# Violet_Usb_Hub.net
KiCad netlist of a schematic drawn in EasyEDA Pro
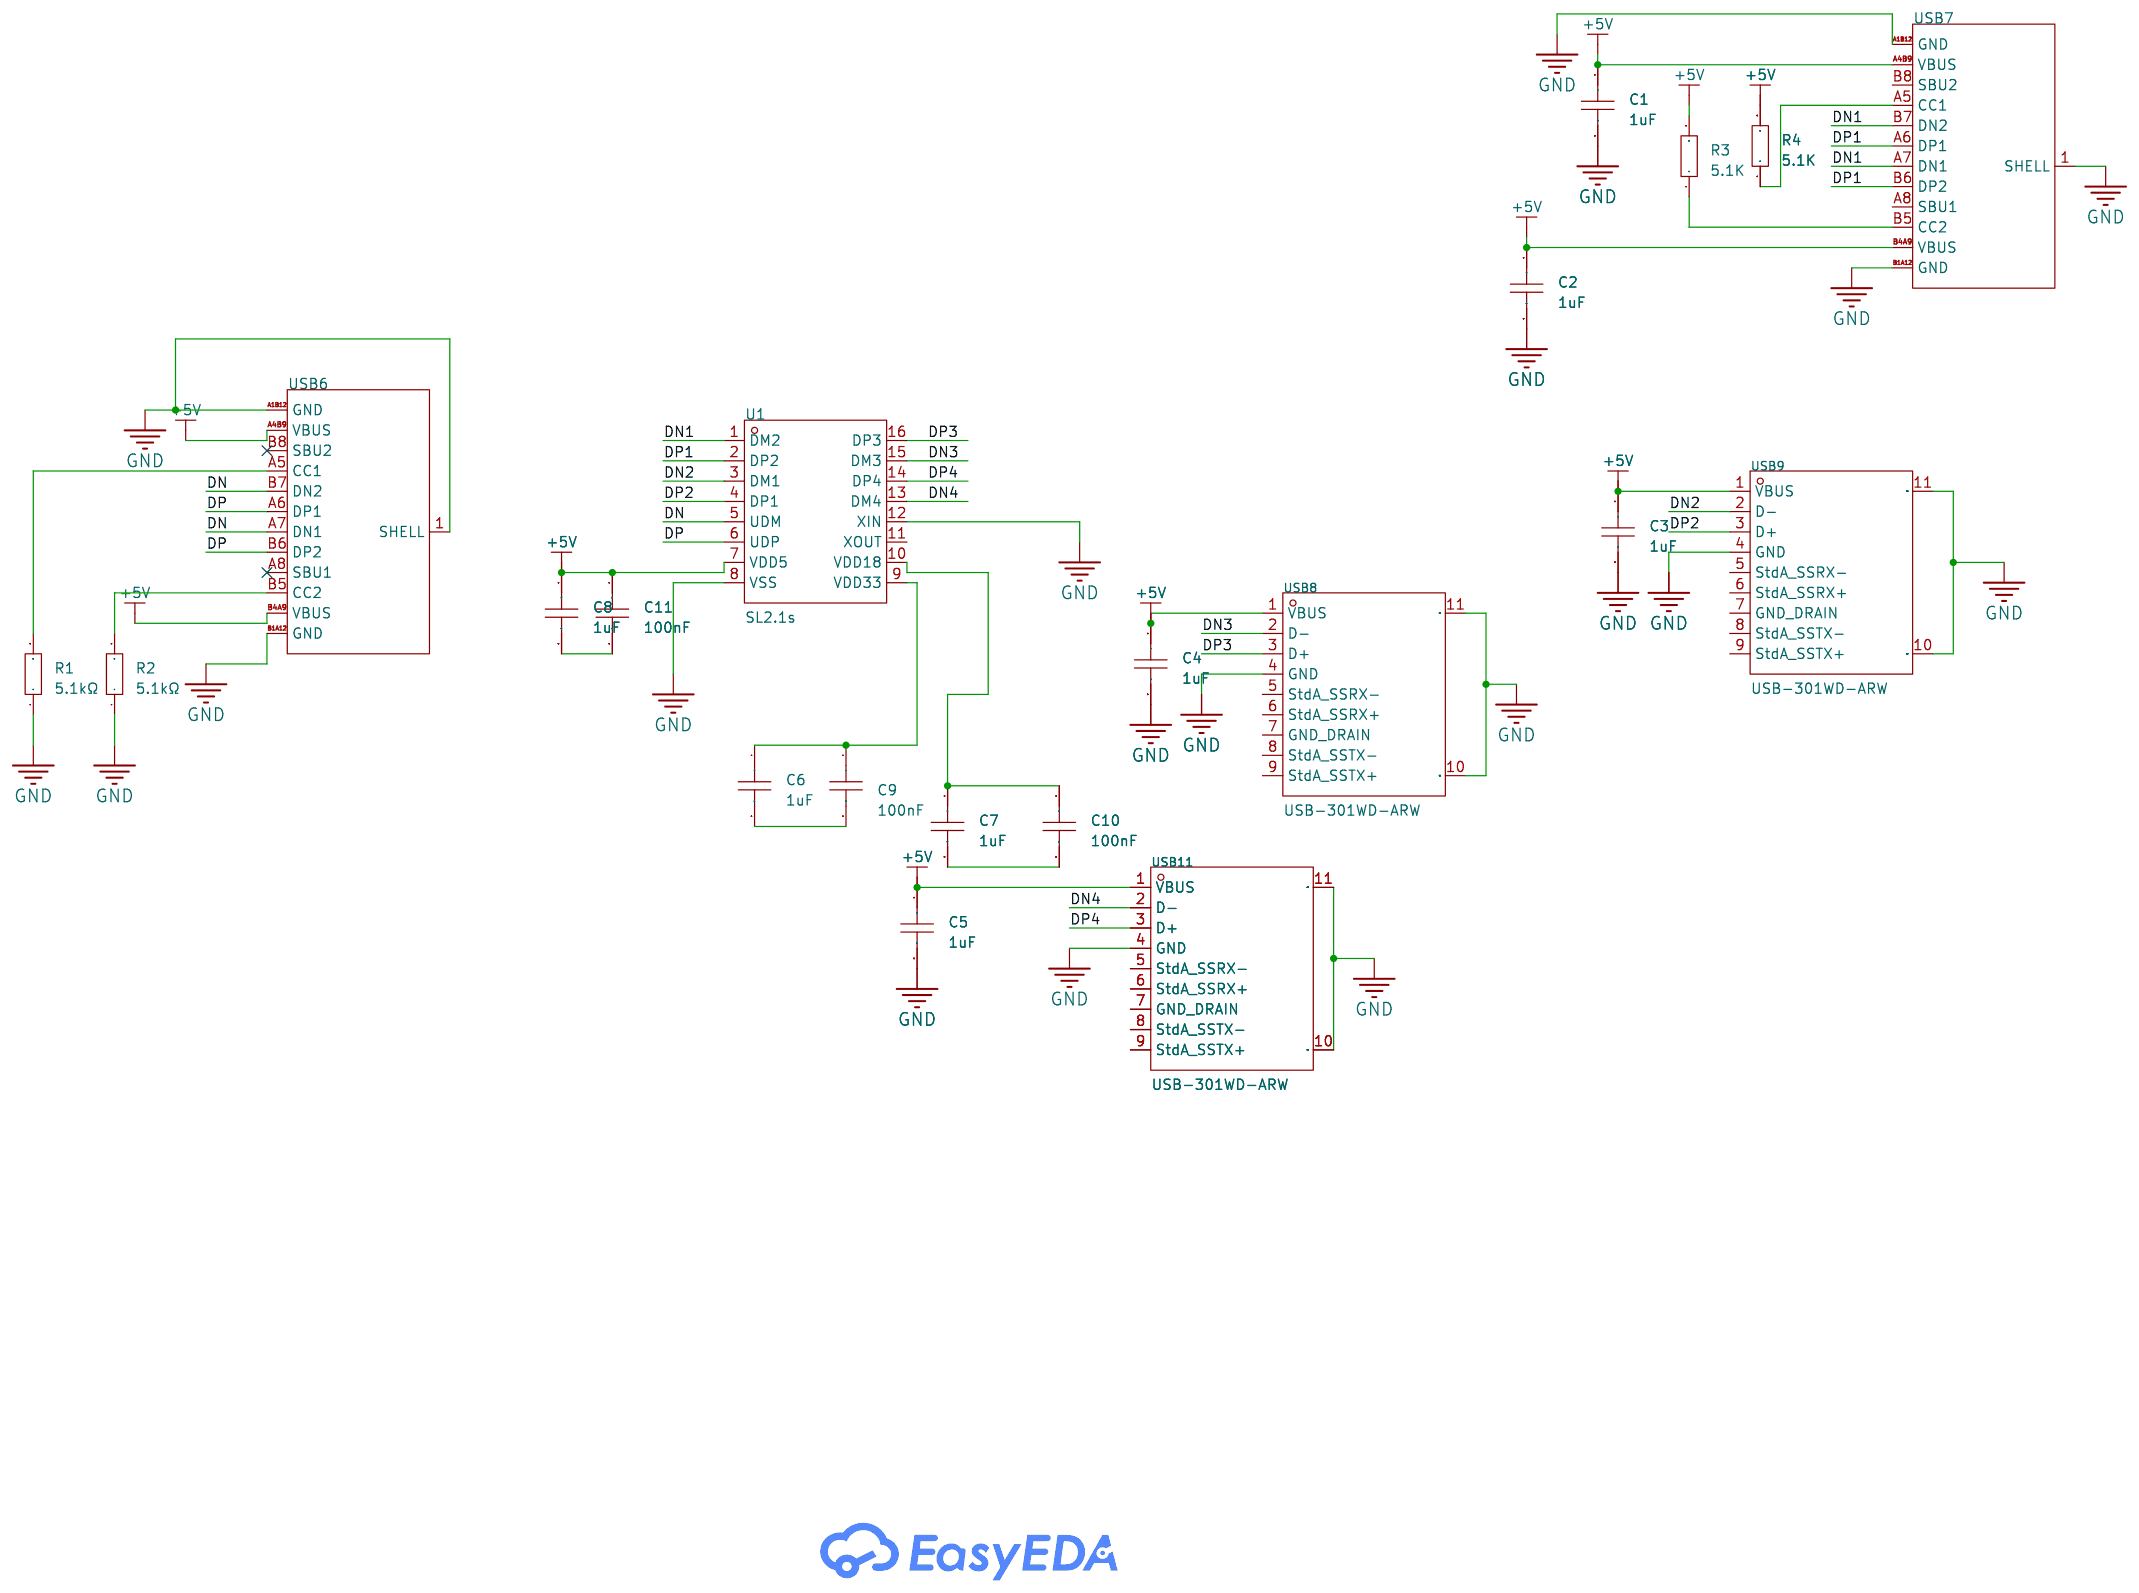
[diagram p0: schematic sheet]

(export (version "E")
  (design (tool "Eeschema 10.0.6"))
  (components
    (comp (ref "C1") (value "1uF") (footprint "easyedapro:C0603") (libsource (lib "easyedapro") (part "CAP")))
    (comp (ref "C2") (value "1uF") (footprint "easyedapro:C0603") (libsource (lib "easyedapro") (part "CAP")))
    (comp (ref "C3") (value "1uF") (footprint "easyedapro:C0603") (libsource (lib "easyedapro") (part "CAP")))
    (comp (ref "C4") (value "1uF") (footprint "easyedapro:C0603") (libsource (lib "easyedapro") (part "CAP")))
    (comp (ref "C5") (value "1uF") (footprint "easyedapro:C0603") (libsource (lib "easyedapro") (part "CAP")))
    (comp (ref "C6") (value "1uF") (footprint "easyedapro:C0603") (libsource (lib "easyedapro") (part "CAP")))
    (comp (ref "C7") (value "1uF") (footprint "easyedapro:C0603") (libsource (lib "easyedapro") (part "CAP")))
    (comp (ref "C8") (value "1uF") (footprint "easyedapro:C0603") (libsource (lib "easyedapro") (part "CAP")))
    (comp (ref "C9")
      (value "100nF")
      (footprint "easyedapro:C0603")
      (libsource (lib "easyedapro") (part "CAP"))
    )
    (comp (ref "C10")
      (value "100nF")
      (footprint "easyedapro:C0603")
      (libsource (lib "easyedapro") (part "CAP"))
    )
    (comp (ref "C11")
      (value "100nF")
      (footprint "easyedapro:C0603")
      (libsource (lib "easyedapro") (part "CAP"))
    )
    (comp (ref "R1")
      (value "5.1kΩ")
      (footprint "easyedapro:R0603")
      (libsource (lib "easyedapro") (part "Res"))
    )
    (comp (ref "R2")
      (value "5.1kΩ")
      (footprint "easyedapro:R0603")
      (libsource (lib "easyedapro") (part "Res"))
    )
    (comp (ref "R3")
      (value "5.1K")
      (footprint "easyedapro:R0603")
      (libsource (lib "easyedapro") (part "Res"))
    )
    (comp (ref "R4")
      (value "5.1K")
      (footprint "easyedapro:R0603")
      (libsource (lib "easyedapro") (part "Res"))
    )
    (comp (ref "U1")
      (value "SL2.1s")
      (footprint "easyedapro:SSOP-16_L4.6-W2.6-P0.53-LS4.0-BL")
      (fields (field (name "Manufacturer") "CoreChips(和芯润德)"))
      (libsource (lib "easyedapro") (part "SL2.1S"))
    )
    (comp (ref "USB6")
      (value "JBL-104312272-E")
      (footprint "easyedapro:USB-C-SMD_JBL-104312272-E")
      (fields (field (name "Manufacturer") "JBL(金比莱)"))
      (libsource (lib "easyedapro") (part "JBL-104312272-E"))
    )
    (comp (ref "USB7")
      (value "JBL-104312272-E")
      (footprint "easyedapro:USB-C-SMD_JBL-104312272-E")
      (fields (field (name "Manufacturer") "JBL(金比莱)"))
      (libsource (lib "easyedapro") (part "JBL-104312272-E"))
    )
    (comp (ref "USB8")
      (value "USB-301WD-ARW")
      (footprint "easyedapro:USB-TH_XUNPU_USB-301WD-ARW")
      (fields (field (name "Manufacturer") "XUNPU(讯普)"))
      (libsource (lib "easyedapro") (part "USB-301WD-ARW"))
    )
    (comp (ref "USB9")
      (value "USB-301WD-ARW")
      (footprint "easyedapro:USB-TH_XUNPU_USB-301WD-ARW")
      (fields (field (name "Manufacturer") "XUNPU(讯普)"))
      (libsource (lib "easyedapro") (part "USB-301WD-ARW"))
    )
    (comp (ref "USB11")
      (value "USB-301WD-ARW")
      (footprint "easyedapro:USB-TH_XUNPU_USB-301WD-ARW")
      (fields (field (name "Manufacturer") "XUNPU(讯普)"))
      (libsource (lib "easyedapro") (part "USB-301WD-ARW"))
    )
  )
  (nets
    (net (code "1") (name "+5V") (class "Default")
      (node (ref "C1") (pin "1") (pinfunction "1_1") (pintype "input"))
      (node (ref "C11") (pin "1") (pinfunction "1_1") (pintype "input"))
      (node (ref "C2") (pin "1") (pinfunction "1_1") (pintype "input"))
      (node (ref "C3") (pin "1") (pinfunction "1_1") (pintype "input"))
      (node (ref "C4") (pin "1") (pinfunction "1_1") (pintype "input"))
      (node (ref "C5") (pin "1") (pinfunction "1_1") (pintype "input"))
      (node (ref "C8") (pin "1") (pinfunction "1_1") (pintype "input"))
      (node (ref "R3") (pin "2") (pinfunction "2_2") (pintype "input"))
      (node (ref "R4") (pin "2") (pinfunction "2_2") (pintype "input"))
      (node (ref "U1") (pin "7") (pinfunction "VDD5_7") (pintype "unspecified"))
      (node (ref "USB11") (pin "1") (pinfunction "VBUS_1") (pintype "input"))
      (node (ref "USB6") (pin "A4B9") (pinfunction "VBUS_A4B9") (pintype "unspecified"))
      (node (ref "USB6") (pin "B4A9") (pinfunction "VBUS_B4A9") (pintype "unspecified"))
      (node (ref "USB7") (pin "A4B9") (pinfunction "VBUS_A4B9") (pintype "unspecified"))
      (node (ref "USB7") (pin "B4A9") (pinfunction "VBUS_B4A9") (pintype "unspecified"))
      (node (ref "USB8") (pin "1") (pinfunction "VBUS_1") (pintype "input"))
      (node (ref "USB9") (pin "1") (pinfunction "VBUS_1") (pintype "input"))
    )
    (net (code "2") (name "/DN") (class "Default")
      (node (ref "U1") (pin "5") (pinfunction "UDM_5") (pintype "unspecified"))
      (node (ref "USB6") (pin "A7") (pinfunction "DN1_A7") (pintype "unspecified"))
      (node (ref "USB6") (pin "B7") (pinfunction "DN2_B7") (pintype "unspecified"))
    )
    (net (code "3") (name "/DN1") (class "Default")
      (node (ref "U1") (pin "1") (pinfunction "DM2_1") (pintype "unspecified"))
      (node (ref "USB7") (pin "A7") (pinfunction "DN1_A7") (pintype "unspecified"))
      (node (ref "USB7") (pin "B7") (pinfunction "DN2_B7") (pintype "unspecified"))
    )
    (net (code "4") (name "/DN2") (class "Default")
      (node (ref "U1") (pin "3") (pinfunction "DM1_3") (pintype "unspecified"))
      (node (ref "USB9") (pin "2") (pinfunction "D-_2") (pintype "input"))
    )
    (net (code "5") (name "/DN3") (class "Default")
      (node (ref "U1") (pin "15") (pinfunction "DM3_15") (pintype "unspecified"))
      (node (ref "USB8") (pin "2") (pinfunction "D-_2") (pintype "input"))
    )
    (net (code "6") (name "/DN4") (class "Default")
      (node (ref "U1") (pin "13") (pinfunction "DM4_13") (pintype "unspecified"))
      (node (ref "USB11") (pin "2") (pinfunction "D-_2") (pintype "input"))
    )
    (net (code "7") (name "/DP") (class "Default")
      (node (ref "U1") (pin "6") (pinfunction "UDP_6") (pintype "unspecified"))
      (node (ref "USB6") (pin "A6") (pinfunction "DP1_A6") (pintype "unspecified"))
      (node (ref "USB6") (pin "B6") (pinfunction "DP2_B6") (pintype "unspecified"))
    )
    (net (code "8") (name "/DP1") (class "Default")
      (node (ref "U1") (pin "2") (pinfunction "DP2_2") (pintype "unspecified"))
      (node (ref "USB7") (pin "A6") (pinfunction "DP1_A6") (pintype "unspecified"))
      (node (ref "USB7") (pin "B6") (pinfunction "DP2_B6") (pintype "unspecified"))
    )
    (net (code "9") (name "/DP2") (class "Default")
      (node (ref "U1") (pin "4") (pinfunction "DP1_4") (pintype "unspecified"))
      (node (ref "USB9") (pin "3") (pinfunction "D+_3") (pintype "input"))
    )
    (net (code "10") (name "/DP3") (class "Default")
      (node (ref "U1") (pin "16") (pinfunction "DP3_16") (pintype "unspecified"))
      (node (ref "USB8") (pin "3") (pinfunction "D+_3") (pintype "input"))
    )
    (net (code "11") (name "/DP4") (class "Default")
      (node (ref "U1") (pin "14") (pinfunction "DP4_14") (pintype "unspecified"))
      (node (ref "USB11") (pin "3") (pinfunction "D+_3") (pintype "input"))
    )
    (net (code "12") (name "GND") (class "Default")
      (node (ref "C1") (pin "2") (pinfunction "2_2") (pintype "input"))
      (node (ref "C2") (pin "2") (pinfunction "2_2") (pintype "input"))
      (node (ref "C3") (pin "2") (pinfunction "2_2") (pintype "input"))
      (node (ref "C4") (pin "2") (pinfunction "2_2") (pintype "input"))
      (node (ref "C5") (pin "2") (pinfunction "2_2") (pintype "input"))
      (node (ref "R1") (pin "1") (pinfunction "1_1") (pintype "input"))
      (node (ref "R2") (pin "1") (pinfunction "1_1") (pintype "input"))
      (node (ref "U1") (pin "12") (pinfunction "XIN_12") (pintype "unspecified"))
      (node (ref "U1") (pin "8") (pinfunction "VSS_8") (pintype "unspecified"))
      (node (ref "USB11") (pin "10") (pinfunction "SHIELD_10") (pintype "input"))
      (node (ref "USB11") (pin "11") (pinfunction "SHIELD_11") (pintype "input"))
      (node (ref "USB11") (pin "4") (pinfunction "GND_4") (pintype "input"))
      (node (ref "USB6") (pin "1") (pinfunction "SHELL_1") (pintype "unspecified"))
      (node (ref "USB6") (pin "A1B12") (pinfunction "GND_A1B12") (pintype "unspecified"))
      (node (ref "USB6") (pin "B1A12") (pinfunction "GND_B1A12") (pintype "unspecified"))
      (node (ref "USB7") (pin "1") (pinfunction "SHELL_1") (pintype "unspecified"))
      (node (ref "USB7") (pin "A1B12") (pinfunction "GND_A1B12") (pintype "unspecified"))
      (node (ref "USB7") (pin "B1A12") (pinfunction "GND_B1A12") (pintype "unspecified"))
      (node (ref "USB8") (pin "10") (pinfunction "SHIELD_10") (pintype "input"))
      (node (ref "USB8") (pin "11") (pinfunction "SHIELD_11") (pintype "input"))
      (node (ref "USB8") (pin "4") (pinfunction "GND_4") (pintype "input"))
      (node (ref "USB9") (pin "10") (pinfunction "SHIELD_10") (pintype "input"))
      (node (ref "USB9") (pin "11") (pinfunction "SHIELD_11") (pintype "input"))
      (node (ref "USB9") (pin "4") (pinfunction "GND_4") (pintype "input"))
    )
    (net (code "13") (name "Net-(C6-Pad2)") (class "Default")
      (node (ref "C6") (pin "2") (pinfunction "2_2") (pintype "input"))
      (node (ref "C9") (pin "2") (pinfunction "2_2") (pintype "input"))
    )
    (net (code "14") (name "Net-(C10-Pad2)") (class "Default")
      (node (ref "C10") (pin "2") (pinfunction "2_2") (pintype "input"))
      (node (ref "C7") (pin "2") (pinfunction "2_2") (pintype "input"))
    )
    (net (code "15") (name "Net-(C11-Pad2)") (class "Default")
      (node (ref "C11") (pin "2") (pinfunction "2_2") (pintype "input"))
      (node (ref "C8") (pin "2") (pinfunction "2_2") (pintype "input"))
    )
    (net (code "16") (name "Net-(U1-VDD18)") (class "Default")
      (node (ref "C10") (pin "1") (pinfunction "1_1") (pintype "input"))
      (node (ref "C7") (pin "1") (pinfunction "1_1") (pintype "input"))
      (node (ref "U1") (pin "10") (pinfunction "VDD18_10") (pintype "unspecified"))
    )
    (net (code "17") (name "Net-(U1-VDD33)") (class "Default")
      (node (ref "C6") (pin "1") (pinfunction "1_1") (pintype "input"))
      (node (ref "C9") (pin "1") (pinfunction "1_1") (pintype "input"))
      (node (ref "U1") (pin "9") (pinfunction "VDD33_9") (pintype "unspecified"))
    )
    (net (code "18") (name "Net-(USB6-CC1)") (class "Default")
      (node (ref "R1") (pin "2") (pinfunction "2_2") (pintype "input"))
      (node (ref "USB6") (pin "A5") (pinfunction "CC1_A5") (pintype "unspecified"))
    )
    (net (code "19") (name "Net-(USB6-CC2)") (class "Default")
      (node (ref "R2") (pin "2") (pinfunction "2_2") (pintype "input"))
      (node (ref "USB6") (pin "B5") (pinfunction "CC2_B5") (pintype "unspecified"))
    )
    (net (code "20") (name "Net-(USB7-CC1)") (class "Default")
      (node (ref "R4") (pin "1") (pinfunction "1_1") (pintype "input"))
      (node (ref "USB7") (pin "A5") (pinfunction "CC1_A5") (pintype "unspecified"))
    )
    (net (code "21") (name "Net-(USB7-CC2)") (class "Default")
      (node (ref "R3") (pin "1") (pinfunction "1_1") (pintype "input"))
      (node (ref "USB7") (pin "B5") (pinfunction "CC2_B5") (pintype "unspecified"))
    )
    (net (code "22") (name "unconnected-(U1-XOUT-Pad11)") (class "Default")
      (node (ref "U1") (pin "11") (pinfunction "XOUT_11") (pintype "unspecified"))
    )
    (net (code "23") (name "unconnected-(USB6-SBU1-PadA8)") (class "Default")
      (node (ref "USB6") (pin "A8") (pinfunction "SBU1_A8") (pintype "unspecified+no_connect"))
    )
    (net (code "24") (name "unconnected-(USB6-SBU2-PadB8)") (class "Default")
      (node (ref "USB6") (pin "B8") (pinfunction "SBU2_B8") (pintype "unspecified+no_connect"))
    )
    (net (code "25") (name "unconnected-(USB7-SBU1-PadA8)") (class "Default")
      (node (ref "USB7") (pin "A8") (pinfunction "SBU1_A8") (pintype "unspecified"))
    )
    (net (code "26") (name "unconnected-(USB7-SBU2-PadB8)") (class "Default")
      (node (ref "USB7") (pin "B8") (pinfunction "SBU2_B8") (pintype "unspecified"))
    )
    (net (code "27") (name "unconnected-(USB8-GND_DRAIN-Pad7)") (class "Default")
      (node (ref "USB8") (pin "7") (pinfunction "GND_DRAIN_7") (pintype "input"))
    )
    (net (code "28") (name "unconnected-(USB8-StdA_SSRX+-Pad6)") (class "Default")
      (node (ref "USB8") (pin "6") (pinfunction "StdA_SSRX+_6") (pintype "input"))
    )
    (net (code "29") (name "unconnected-(USB8-StdA_SSRX--Pad5)") (class "Default")
      (node (ref "USB8") (pin "5") (pinfunction "StdA_SSRX-_5") (pintype "input"))
    )
    (net (code "30") (name "unconnected-(USB8-StdA_SSTX+-Pad9)") (class "Default")
      (node (ref "USB8") (pin "9") (pinfunction "StdA_SSTX+_9") (pintype "input"))
    )
    (net (code "31") (name "unconnected-(USB8-StdA_SSTX--Pad8)") (class "Default")
      (node (ref "USB8") (pin "8") (pinfunction "StdA_SSTX-_8") (pintype "input"))
    )
    (net (code "32") (name "unconnected-(USB9-GND_DRAIN-Pad7)") (class "Default")
      (node (ref "USB9") (pin "7") (pinfunction "GND_DRAIN_7") (pintype "input"))
    )
    (net (code "33") (name "unconnected-(USB9-StdA_SSRX+-Pad6)") (class "Default")
      (node (ref "USB9") (pin "6") (pinfunction "StdA_SSRX+_6") (pintype "input"))
    )
    (net (code "34") (name "unconnected-(USB9-StdA_SSRX--Pad5)") (class "Default")
      (node (ref "USB9") (pin "5") (pinfunction "StdA_SSRX-_5") (pintype "input"))
    )
    (net (code "35") (name "unconnected-(USB9-StdA_SSTX+-Pad9)") (class "Default")
      (node (ref "USB9") (pin "9") (pinfunction "StdA_SSTX+_9") (pintype "input"))
    )
    (net (code "36") (name "unconnected-(USB9-StdA_SSTX--Pad8)") (class "Default")
      (node (ref "USB9") (pin "8") (pinfunction "StdA_SSTX-_8") (pintype "input"))
    )
    (net (code "37") (name "unconnected-(USB11-GND_DRAIN-Pad7)") (class "Default")
      (node (ref "USB11") (pin "7") (pinfunction "GND_DRAIN_7") (pintype "input"))
    )
    (net (code "38") (name "unconnected-(USB11-StdA_SSRX+-Pad6)") (class "Default")
      (node (ref "USB11") (pin "6") (pinfunction "StdA_SSRX+_6") (pintype "input"))
    )
    (net (code "39") (name "unconnected-(USB11-StdA_SSRX--Pad5)") (class "Default")
      (node (ref "USB11") (pin "5") (pinfunction "StdA_SSRX-_5") (pintype "input"))
    )
    (net (code "40") (name "unconnected-(USB11-StdA_SSTX+-Pad9)") (class "Default")
      (node (ref "USB11") (pin "9") (pinfunction "StdA_SSTX+_9") (pintype "input"))
    )
    (net (code "41") (name "unconnected-(USB11-StdA_SSTX--Pad8)") (class "Default")
      (node (ref "USB11") (pin "8") (pinfunction "StdA_SSTX-_8") (pintype "input"))
    )
  )
)
